# Qwiic_RFID_-_ID12LA.net
KiCad netlist of a schematic drawn in EAGLE
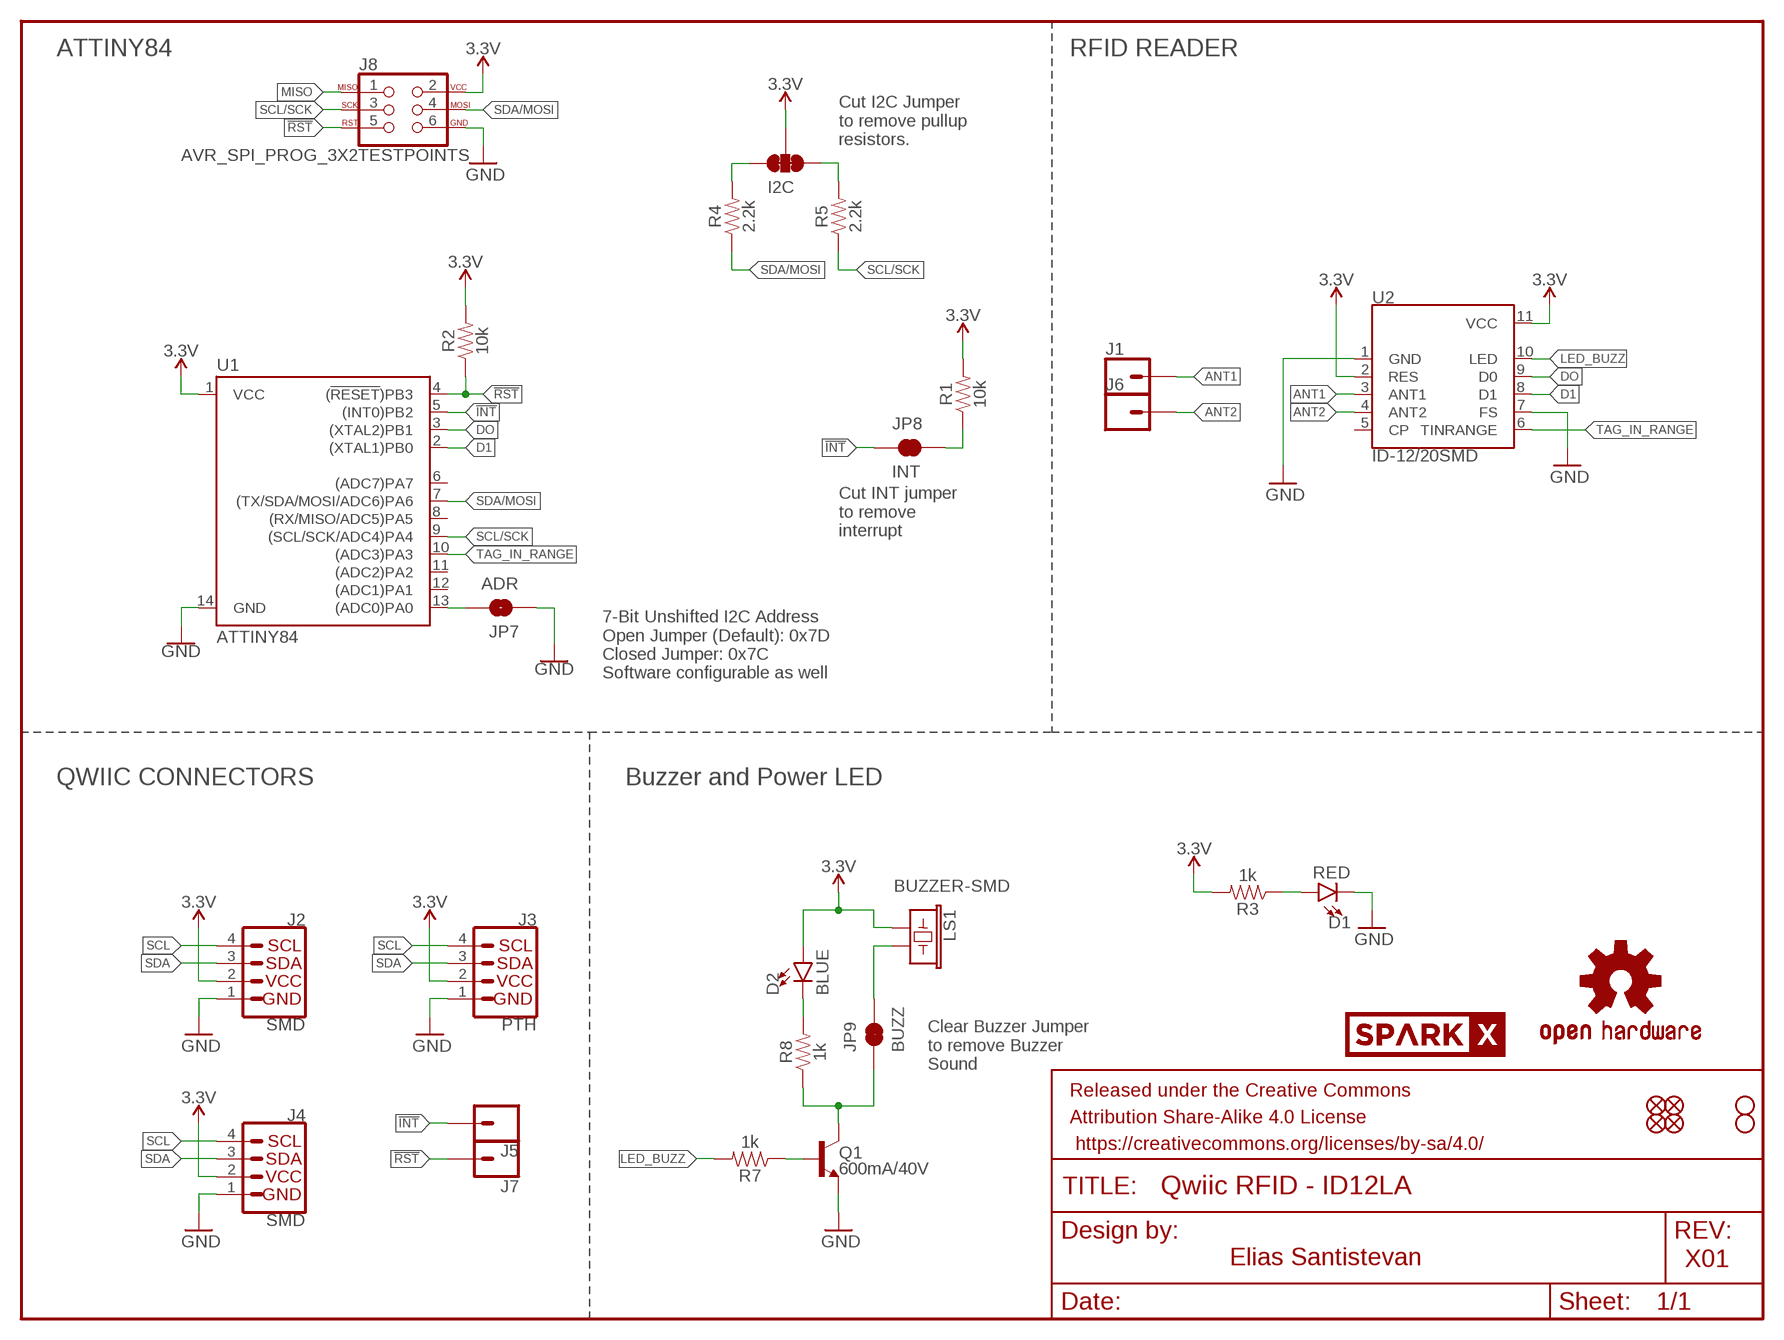
[diagram p0: schematic, sheet 1]

(export (version "E")
  (design (tool "Eeschema 10.0.6"))
  (components
    (comp (ref "D1")
      (value "RED")
      (footprint "eagle-import:LED-0603")
      (libsource (lib "eagle-import") (part "LED-RED0603"))
    )
    (comp (ref "D2")
      (value "BLUE")
      (footprint "eagle-import:LED-0603")
      (libsource (lib "eagle-import") (part "LED-BLUE0603"))
    )
    (comp (ref "FRAME1")
      (value "FRAME-LETTER")
      (footprint "eagle-import:CREATIVE_COMMONS")
      (libsource (lib "eagle-import") (part "FRAME-LETTER"))
    )
    (comp (ref "I2C")
      (value "JUMPER-SMT_3_2-NC_TRACE_SILK")
      (footprint "eagle-import:SMT-JUMPER_3_2-NC_TRACE_SILK")
      (libsource (lib "eagle-import") (part "JUMPER-SMT_3_2-NC_TRACE_SILK"))
    )
    (comp (ref "J1")
      (value "CONN_01PTH_NO_SILK_YES_STOP")
      (footprint "eagle-import:1X01_NO_SILK")
      (libsource (lib "eagle-import") (part "CONN_01PTH_NO_SILK_YES_STOP"))
    )
    (comp (ref "J2")
      (value "SMD")
      (footprint "eagle-import:1X04_1MM_RA")
      (libsource (lib "eagle-import") (part "I2C_STANDARDJS-1MM"))
    )
    (comp (ref "J3")
      (value "PTH")
      (footprint "eagle-import:1X04_NO_SILK")
      (libsource (lib "eagle-import") (part "I2C_STANDARD_NO_SILK"))
    )
    (comp (ref "J4")
      (value "SMD")
      (footprint "eagle-import:1X04_1MM_RA")
      (libsource (lib "eagle-import") (part "I2C_STANDARDJS-1MM"))
    )
    (comp (ref "J5")
      (value "CONN_01PTH_NO_SILK_YES_STOP")
      (footprint "eagle-import:1X01_NO_SILK")
      (libsource (lib "eagle-import") (part "CONN_01PTH_NO_SILK_YES_STOP"))
    )
    (comp (ref "J6")
      (value "CONN_01PTH_NO_SILK_YES_STOP")
      (footprint "eagle-import:1X01_NO_SILK")
      (libsource (lib "eagle-import") (part "CONN_01PTH_NO_SILK_YES_STOP"))
    )
    (comp (ref "J7")
      (value "CONN_01PTH_NO_SILK_YES_STOP")
      (footprint "eagle-import:1X01_NO_SILK")
      (libsource (lib "eagle-import") (part "CONN_01PTH_NO_SILK_YES_STOP"))
    )
    (comp (ref "J8")
      (value "AVR_SPI_PROG_3X2TESTPOINTS")
      (footprint "eagle-import:2X3_TEST_POINTS")
      (libsource (lib "eagle-import") (part "AVR_SPI_PROG_3X2TESTPOINTS"))
    )
    (comp (ref "JP1")
      (value "FIDUCIALUFIDUCIAL")
      (footprint "eagle-import:MICRO-FIDUCIAL")
      (libsource (lib "eagle-import") (part "FIDUCIALUFIDUCIAL"))
    )
    (comp (ref "JP2")
      (value "FIDUCIALUFIDUCIAL")
      (footprint "eagle-import:MICRO-FIDUCIAL")
      (libsource (lib "eagle-import") (part "FIDUCIALUFIDUCIAL"))
    )
    (comp (ref "JP3")
      (value "STAND-OFF")
      (footprint "eagle-import:STAND-OFF")
      (libsource (lib "eagle-import") (part "STAND-OFF"))
    )
    (comp (ref "JP4")
      (value "STAND-OFF")
      (footprint "eagle-import:STAND-OFF")
      (libsource (lib "eagle-import") (part "STAND-OFF"))
    )
    (comp (ref "JP5")
      (value "FIDUCIALUFIDUCIAL")
      (footprint "eagle-import:MICRO-FIDUCIAL")
      (libsource (lib "eagle-import") (part "FIDUCIALUFIDUCIAL"))
    )
    (comp (ref "JP6")
      (value "FIDUCIALUFIDUCIAL")
      (footprint "eagle-import:MICRO-FIDUCIAL")
      (libsource (lib "eagle-import") (part "FIDUCIALUFIDUCIAL"))
    )
    (comp (ref "JP7")
      (value "ADR")
      (footprint "eagle-import:SMT-JUMPER_2_NO_SILK")
      (libsource (lib "eagle-import") (part "JUMPER-SMT_2_NO_SILK"))
    )
    (comp (ref "JP8")
      (value "INT")
      (footprint "eagle-import:SMT-JUMPER_2_NC_TRACE_SILK")
      (libsource (lib "eagle-import") (part "JUMPER-SMT_2_NC_TRACE_SILK"))
    )
    (comp (ref "JP9")
      (value "BUZZ")
      (footprint "eagle-import:SMT-JUMPER_2_NC_TRACE_SILK")
      (libsource (lib "eagle-import") (part "JUMPER-SMT_2_NC_TRACE_SILK"))
    )
    (comp (ref "LOGO1")
      (value "OSHW-LOGOMINI")
      (footprint "eagle-import:OSHW-LOGO-MINI")
      (libsource (lib "eagle-import") (part "OSHW-LOGOMINI"))
    )
    (comp (ref "LS1")
      (value "BUZZER-SMD")
      (footprint "eagle-import:BUZZER-CCV")
      (libsource (lib "eagle-import") (part "BUZZER-SMD"))
    )
    (comp (ref "Q1")
      (value "600mA/40V")
      (footprint "eagle-import:SOT23-3")
      (libsource (lib "eagle-import") (part "TRANS_NPN-MMBT2222AL"))
    )
    (comp (ref "R1")
      (value "10k")
      (footprint "eagle-import:0603")
      (libsource (lib "eagle-import") (part "10KOHM-0603-1/10W-1%"))
    )
    (comp (ref "R2")
      (value "10k")
      (footprint "eagle-import:0603")
      (libsource (lib "eagle-import") (part "10KOHM-0603-1/10W-1%"))
    )
    (comp (ref "R3")
      (value "1k")
      (footprint "eagle-import:0603")
      (libsource (lib "eagle-import") (part "1KOHM-0603-1/10W-1%"))
    )
    (comp (ref "R4")
      (value "2.2k")
      (footprint "eagle-import:0603")
      (libsource (lib "eagle-import") (part "2.2KOHM-0603-1/10W-1%"))
    )
    (comp (ref "R5")
      (value "2.2k")
      (footprint "eagle-import:0603")
      (libsource (lib "eagle-import") (part "2.2KOHM-0603-1/10W-1%"))
    )
    (comp (ref "R7")
      (value "1k")
      (footprint "eagle-import:0603")
      (libsource (lib "eagle-import") (part "1KOHM-0603-1/10W-1%"))
    )
    (comp (ref "R8")
      (value "1k")
      (footprint "eagle-import:0603")
      (libsource (lib "eagle-import") (part "1KOHM-0603-1/10W-1%"))
    )
    (comp (ref "U$4")
      (value "SPARKX-LOGO3")
      (footprint "eagle-import:SPARKX-SMALL")
      (libsource (lib "eagle-import") (part "SPARKX-LOGO3"))
    )
    (comp (ref "U1")
      (value "ATTINY84")
      (footprint "eagle-import:SO14")
      (libsource (lib "eagle-import") (part "ATTINY84"))
    )
    (comp (ref "U2")
      (value "ID-12/20SMD")
      (footprint "eagle-import:ID-12_SMD")
      (libsource (lib "eagle-import") (part "ID-12/20SMD"))
    )
  )
  (nets
    (net (code "1") (name "/~{INT}") (class "Default")
      (node (ref "J5") (pin "1") (pinfunction "1_1") (pintype "passive"))
      (node (ref "JP8") (pin "1") (pinfunction "1_1") (pintype "passive"))
      (node (ref "U1") (pin "5") (pinfunction "(INT0)PB2_5") (pintype "bidirectional"))
    )
    (net (code "2") (name "/~{RST}") (class "Default")
      (node (ref "J7") (pin "1") (pinfunction "1_1") (pintype "passive"))
      (node (ref "J8") (pin "5") (pinfunction "5_5") (pintype "passive"))
      (node (ref "R2") (pin "1") (pinfunction "1_1") (pintype "passive"))
      (node (ref "U1") (pin "4") (pinfunction "(~{RESET})PB3_4") (pintype "bidirectional"))
    )
    (net (code "3") (name "3.3V") (class "Default")
      (node (ref "D2") (pin "A") (pinfunction "A_A") (pintype "passive"))
      (node (ref "I2C") (pin "2") (pinfunction "2_2") (pintype "passive"))
      (node (ref "J2") (pin "2") (pinfunction "VCC_2") (pintype "power_in"))
      (node (ref "J3") (pin "2") (pinfunction "VCC_2") (pintype "power_in"))
      (node (ref "J4") (pin "2") (pinfunction "VCC_2") (pintype "power_in"))
      (node (ref "J8") (pin "2") (pinfunction "2_2") (pintype "passive"))
      (node (ref "LS1") (pin "+") (pinfunction "1_+") (pintype "passive"))
      (node (ref "R1") (pin "2") (pinfunction "2_2") (pintype "passive"))
      (node (ref "R2") (pin "2") (pinfunction "2_2") (pintype "passive"))
      (node (ref "R3") (pin "2") (pinfunction "2_2") (pintype "passive"))
      (node (ref "U1") (pin "1") (pinfunction "VCC_1") (pintype "bidirectional"))
      (node (ref "U2") (pin "11") (pinfunction "VCC_11") (pintype "bidirectional"))
      (node (ref "U2") (pin "2") (pinfunction "RES_2") (pintype "bidirectional"))
    )
    (net (code "4") (name "ANT1") (class "Default")
      (node (ref "J1") (pin "1") (pinfunction "1_1") (pintype "passive"))
      (node (ref "U2") (pin "3") (pinfunction "ANT1_3") (pintype "bidirectional"))
    )
    (net (code "5") (name "ANT2") (class "Default")
      (node (ref "J6") (pin "1") (pinfunction "1_1") (pintype "passive"))
      (node (ref "U2") (pin "4") (pinfunction "ANT2_4") (pintype "bidirectional"))
    )
    (net (code "6") (name "D1") (class "Default")
      (node (ref "U1") (pin "2") (pinfunction "(XTAL1)PB0_2") (pintype "bidirectional"))
      (node (ref "U2") (pin "8") (pinfunction "D1_8") (pintype "bidirectional"))
    )
    (net (code "7") (name "DO") (class "Default")
      (node (ref "U1") (pin "3") (pinfunction "(XTAL2)PB1_3") (pintype "bidirectional"))
      (node (ref "U2") (pin "9") (pinfunction "D0_9") (pintype "bidirectional"))
    )
    (net (code "8") (name "GND") (class "Default")
      (node (ref "D1") (pin "C") (pinfunction "C_C") (pintype "passive"))
      (node (ref "J2") (pin "1") (pinfunction "GND_1") (pintype "power_in"))
      (node (ref "J3") (pin "1") (pinfunction "GND_1") (pintype "power_in"))
      (node (ref "J4") (pin "1") (pinfunction "GND_1") (pintype "power_in"))
      (node (ref "J8") (pin "6") (pinfunction "6_6") (pintype "passive"))
      (node (ref "JP7") (pin "1") (pinfunction "1_1") (pintype "passive"))
      (node (ref "Q1") (pin "2") (pinfunction "E_2") (pintype "passive"))
      (node (ref "U1") (pin "14") (pinfunction "GND_14") (pintype "bidirectional"))
      (node (ref "U2") (pin "1") (pinfunction "GND_1") (pintype "bidirectional"))
      (node (ref "U2") (pin "7") (pinfunction "FS_7") (pintype "bidirectional"))
    )
    (net (code "9") (name "LED_BUZZ") (class "Default")
      (node (ref "R7") (pin "2") (pinfunction "2_2") (pintype "passive"))
      (node (ref "U2") (pin "10") (pinfunction "LED_10") (pintype "bidirectional"))
    )
    (net (code "10") (name "MISO") (class "Default")
      (node (ref "J8") (pin "1") (pinfunction "1_1") (pintype "passive"))
    )
    (net (code "11") (name "Net-(D1-PadA)") (class "Default")
      (node (ref "D1") (pin "A") (pinfunction "A_A") (pintype "passive"))
      (node (ref "R3") (pin "1") (pinfunction "1_1") (pintype "passive"))
    )
    (net (code "12") (name "Net-(D2-PadC)") (class "Default")
      (node (ref "D2") (pin "C") (pinfunction "C_C") (pintype "passive"))
      (node (ref "R8") (pin "2") (pinfunction "2_2") (pintype "passive"))
    )
    (net (code "13") (name "Net-(I2C-Pad1)") (class "Default")
      (node (ref "I2C") (pin "1") (pinfunction "1_1") (pintype "passive"))
      (node (ref "R5") (pin "2") (pinfunction "2_2") (pintype "passive"))
    )
    (net (code "14") (name "Net-(I2C-Pad3)") (class "Default")
      (node (ref "I2C") (pin "3") (pinfunction "3_3") (pintype "passive"))
      (node (ref "R4") (pin "2") (pinfunction "2_2") (pintype "passive"))
    )
    (net (code "15") (name "Net-(JP8-Pad2)") (class "Default")
      (node (ref "JP8") (pin "2") (pinfunction "2_2") (pintype "passive"))
      (node (ref "R1") (pin "1") (pinfunction "1_1") (pintype "passive"))
    )
    (net (code "16") (name "Net-(LS1-2)") (class "Default")
      (node (ref "JP9") (pin "2") (pinfunction "2_2") (pintype "passive"))
      (node (ref "LS1") (pin "-") (pinfunction "2_-") (pintype "passive"))
    )
    (net (code "17") (name "Net-(Q1-B)") (class "Default")
      (node (ref "Q1") (pin "1") (pinfunction "B_1") (pintype "passive"))
      (node (ref "R7") (pin "1") (pinfunction "1_1") (pintype "passive"))
    )
    (net (code "18") (name "Net-(Q1-C)") (class "Default")
      (node (ref "JP9") (pin "1") (pinfunction "1_1") (pintype "passive"))
      (node (ref "Q1") (pin "3") (pinfunction "C_3") (pintype "passive"))
      (node (ref "R8") (pin "1") (pinfunction "1_1") (pintype "passive"))
    )
    (net (code "19") (name "Net-(U1-(ADC0)PA0)") (class "Default")
      (node (ref "JP7") (pin "2") (pinfunction "2_2") (pintype "passive"))
      (node (ref "U1") (pin "13") (pinfunction "(ADC0)PA0_13") (pintype "bidirectional"))
    )
    (net (code "20") (name "SCL") (class "Default")
      (node (ref "J2") (pin "4") (pinfunction "SCL_4") (pintype "passive"))
      (node (ref "J3") (pin "4") (pinfunction "SCL_4") (pintype "passive"))
      (node (ref "J4") (pin "4") (pinfunction "SCL_4") (pintype "passive"))
    )
    (net (code "21") (name "SCL{slash}SCK") (class "Default")
      (node (ref "J8") (pin "3") (pinfunction "3_3") (pintype "passive"))
      (node (ref "R5") (pin "1") (pinfunction "1_1") (pintype "passive"))
      (node (ref "U1") (pin "9") (pinfunction "(SCL/SCK/ADC4)PA4_9") (pintype "bidirectional"))
    )
    (net (code "22") (name "SDA") (class "Default")
      (node (ref "J2") (pin "3") (pinfunction "SDA_3") (pintype "passive"))
      (node (ref "J3") (pin "3") (pinfunction "SDA_3") (pintype "passive"))
      (node (ref "J4") (pin "3") (pinfunction "SDA_3") (pintype "passive"))
    )
    (net (code "23") (name "SDA{slash}MOSI") (class "Default")
      (node (ref "J8") (pin "4") (pinfunction "4_4") (pintype "passive"))
      (node (ref "R4") (pin "1") (pinfunction "1_1") (pintype "passive"))
      (node (ref "U1") (pin "7") (pinfunction "(TX/SDA/MOSI/ADC6)PA6_7") (pintype "bidirectional"))
    )
    (net (code "24") (name "TAG_IN_RANGE") (class "Default")
      (node (ref "U1") (pin "10") (pinfunction "(ADC3)PA3_10") (pintype "bidirectional"))
      (node (ref "U2") (pin "6") (pinfunction "TINRANGE_6") (pintype "bidirectional"))
    )
    (net (code "25") (name "unconnected-(U1-(ADC1)PA1-Pad12)") (class "Default")
      (node (ref "U1") (pin "12") (pinfunction "(ADC1)PA1_12") (pintype "bidirectional"))
    )
    (net (code "26") (name "unconnected-(U1-(ADC2)PA2-Pad11)") (class "Default")
      (node (ref "U1") (pin "11") (pinfunction "(ADC2)PA2_11") (pintype "bidirectional"))
    )
    (net (code "27") (name "unconnected-(U1-(ADC7)PA7-Pad6)") (class "Default")
      (node (ref "U1") (pin "6") (pinfunction "(ADC7)PA7_6") (pintype "bidirectional"))
    )
    (net (code "28") (name "unconnected-(U1-(RX{slash}MISO{slash}ADC5)PA5-Pad8)") (class "Default")
      (node (ref "U1") (pin "8") (pinfunction "(RX/MISO/ADC5)PA5_8") (pintype "bidirectional"))
    )
    (net (code "29") (name "unconnected-(U2-CP-Pad5)") (class "Default")
      (node (ref "U2") (pin "5") (pinfunction "CP_5") (pintype "bidirectional"))
    )
  )
)
